# SCH___2023-12-28.net
KiCad netlist of a schematic drawn in EasyEDA
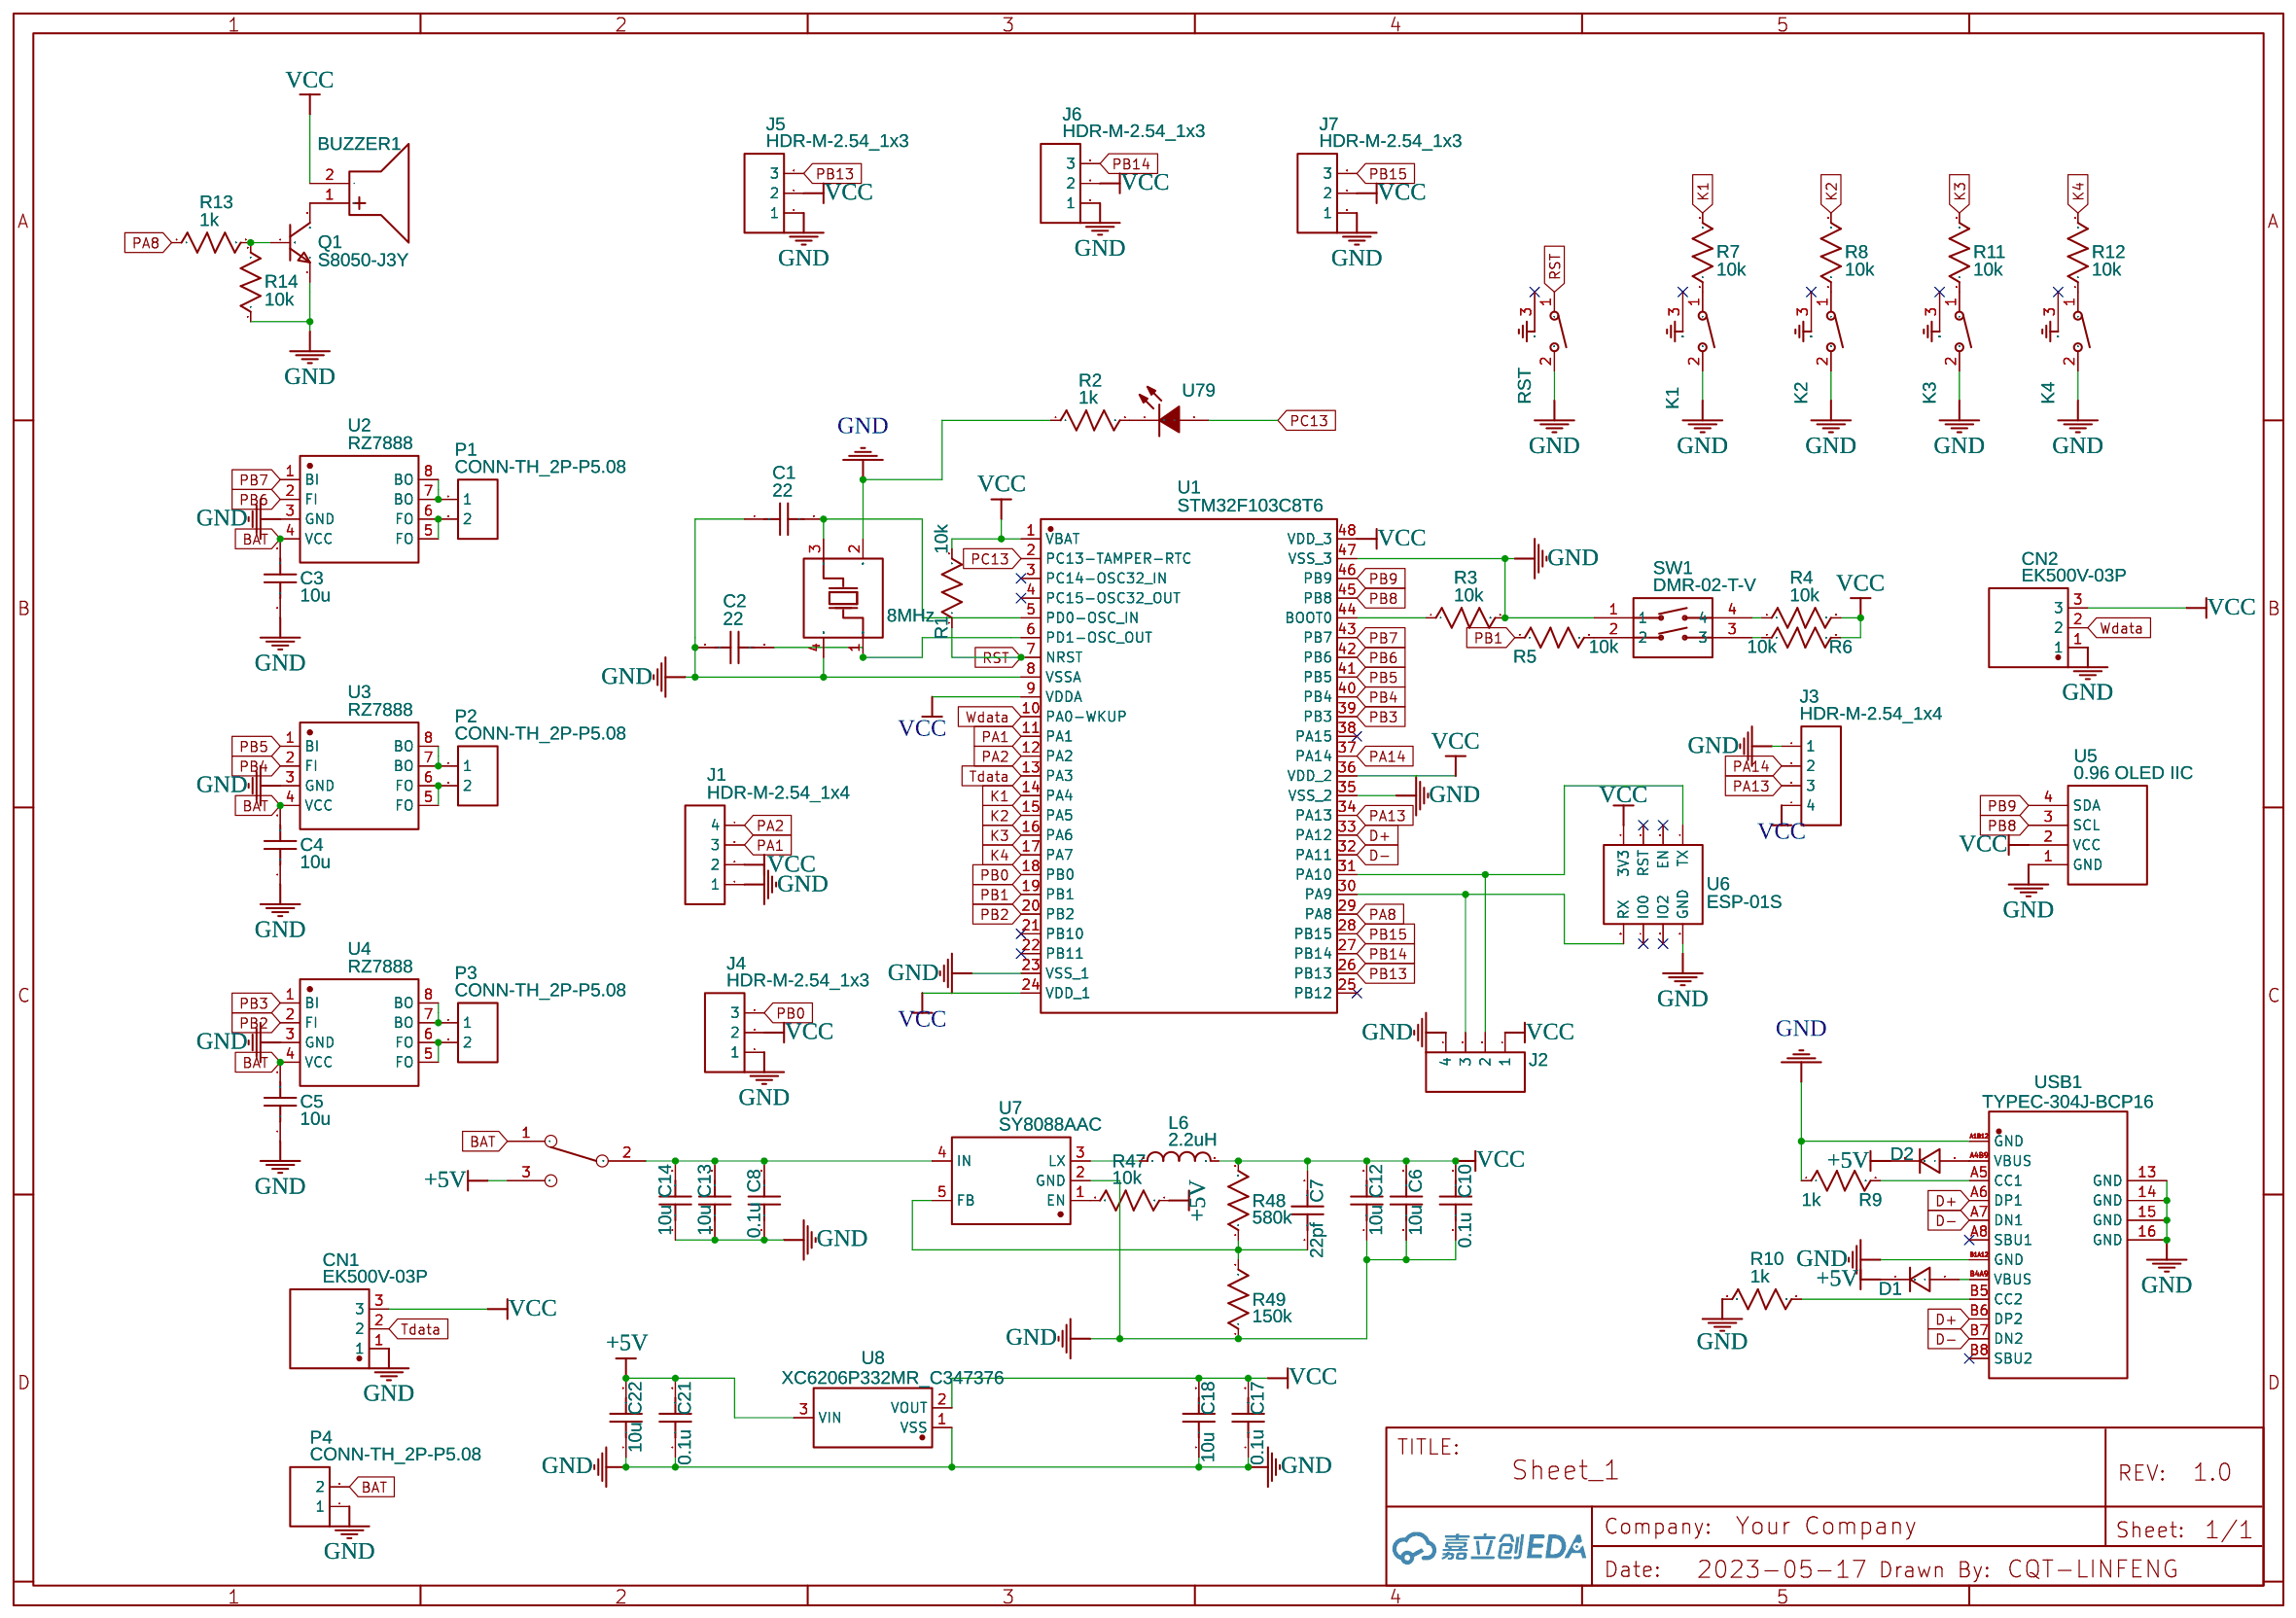
[diagram p0: schematic sheet]

(export (version "E")
  (design (tool "Eeschema 10.0.6"))
  (components
    (comp (ref "BUZZER1")
      (value "有源蜂鸣器直径9*5.5MM3V")
      (fields
        (field (name "BOM_Manufacturer Part") "有源蜂鸣器直径9*5.5mm3V")
        (field (name "BOM_Supplier Part") "C9900012728")
      )
      (libsource (lib "") (part "有源蜂鸣器直径9*5.5MM3V"))
    )
    (comp (ref "C1") (value "22") (libsource (lib "") (part "C_0402_US_1")))
    (comp (ref "C2") (value "22") (libsource (lib "") (part "C_0402_US_1")))
    (comp (ref "C3") (value "10u") (libsource (lib "") (part "C_0402_US")))
    (comp (ref "C4") (value "10u") (libsource (lib "") (part "C_0402_US")))
    (comp (ref "C5") (value "10u") (libsource (lib "") (part "C_0402_US")))
    (comp (ref "C6") (value "10u") (libsource (lib "") (part "C_0402_US")))
    (comp (ref "C7") (value "22pf") (libsource (lib "") (part "C_0402_US")))
    (comp (ref "C8") (value "0.1u") (libsource (lib "") (part "C_0402_US")))
    (comp (ref "C10") (value "0.1u") (libsource (lib "") (part "C_0402_US")))
    (comp (ref "C12") (value "10u") (libsource (lib "") (part "C_0402_US")))
    (comp (ref "C13") (value "10u") (libsource (lib "") (part "C_0402_US")))
    (comp (ref "C14") (value "10u") (libsource (lib "") (part "C_0402_US")))
    (comp (ref "C17") (value "0.1u") (libsource (lib "") (part "C_0402_US")))
    (comp (ref "C18") (value "10u") (libsource (lib "") (part "C_0402_US")))
    (comp (ref "C21") (value "0.1u") (libsource (lib "") (part "C_0402_US")))
    (comp (ref "C22") (value "10u") (libsource (lib "") (part "C_0402_US")))
    (comp (ref "CN1")
      (value "EK500V-03P")
      (fields (field (name "BOM_Supplier Part") "C182803"))
      (libsource (lib "") (part "EK500V-03P"))
    )
    (comp (ref "CN2")
      (value "EK500V-03P")
      (fields (field (name "BOM_Supplier Part") "C182803"))
      (libsource (lib "") (part "EK500V-03P"))
    )
    (comp (ref "D1")
      (value "1N4148WSG")
      (fields (field (name "BOM_Supplier Part") "C380926"))
      (libsource (lib "") (part "1N4148WSG"))
    )
    (comp (ref "D2")
      (value "1N4148WSG")
      (fields (field (name "BOM_Supplier Part") "C380926"))
      (libsource (lib "") (part "1N4148WSG"))
    )
    (comp (ref "ENABLE1") (value "SS-12D00-G4") (libsource (lib "") (part "SS-12D00-G4")))
    (comp (ref "J1")
      (value "HDR-M-2.54_1x4")
      (fields (field (name "BOM_Supplier Part") "C124378"))
      (libsource (lib "") (part "HDR-M-2.54_1x4_1"))
    )
    (comp (ref "J2")
      (value "HDR-M-2.54_1x4")
      (fields (field (name "BOM_Supplier Part") "C124378"))
      (libsource (lib "") (part "HDR-M-2.54_1x4"))
    )
    (comp (ref "J3")
      (value "HDR-M-2.54_1x4")
      (fields (field (name "BOM_Supplier Part") "C124378"))
      (libsource (lib "") (part "HDR-M-2.54_1x4_2"))
    )
    (comp (ref "J4")
      (value "HDR-M-2.54_1x3")
      (fields (field (name "BOM_Supplier Part") "C180248"))
      (libsource (lib "") (part "HDR-M-2.54_1x3"))
    )
    (comp (ref "J5")
      (value "HDR-M-2.54_1x3")
      (fields (field (name "BOM_Supplier Part") "C180248"))
      (libsource (lib "") (part "HDR-M-2.54_1x3"))
    )
    (comp (ref "J6")
      (value "HDR-M-2.54_1x3")
      (fields (field (name "BOM_Supplier Part") "C180248"))
      (libsource (lib "") (part "HDR-M-2.54_1x3"))
    )
    (comp (ref "J7")
      (value "HDR-M-2.54_1x3")
      (fields (field (name "BOM_Supplier Part") "C180248"))
      (libsource (lib "") (part "HDR-M-2.54_1x3"))
    )
    (comp (ref "K1") (value "侧按键") (libsource (lib "") (part "侧按键")))
    (comp (ref "K2") (value "侧按键") (libsource (lib "") (part "侧按键")))
    (comp (ref "K3") (value "侧按键") (libsource (lib "") (part "侧按键")))
    (comp (ref "K4") (value "侧按键") (libsource (lib "") (part "侧按键")))
    (comp (ref "L6")
      (value "2.2uH")
      (fields
        (field (name "BOM_Manufacturer Part") "SMTDR32-2R2M")
        (field (name "BOM_Supplier Part") "C326182")
      )
      (libsource (lib "") (part "SMTDR32-2R2M"))
    )
    (comp (ref "P1") (value "CONN-TH_2P-P5.08") (libsource (lib "") (part "CONN-TH_2P-P5.08")))
    (comp (ref "P2") (value "CONN-TH_2P-P5.08") (libsource (lib "") (part "CONN-TH_2P-P5.08")))
    (comp (ref "P3") (value "CONN-TH_2P-P5.08") (libsource (lib "") (part "CONN-TH_2P-P5.08")))
    (comp (ref "P4") (value "CONN-TH_2P-P5.08") (libsource (lib "") (part "CONN-TH_2P-P5.08_1")))
    (comp (ref "Q1")
      (value "S8050-J3Y")
      (fields (field (name "BOM_Supplier Part") "C364312"))
      (libsource (lib "") (part "S8050-J3Y"))
    )
    (comp (ref "R1") (value "10k") (libsource (lib "") (part "R_0402_US")))
    (comp (ref "R2") (value "1k") (libsource (lib "") (part "R_0402_US_1")))
    (comp (ref "R3") (value "10k") (libsource (lib "") (part "R_0402_US_1")))
    (comp (ref "R4") (value "10k") (libsource (lib "") (part "R_0402_US_1")))
    (comp (ref "R5") (value "10k") (libsource (lib "") (part "R_0402_US_1")))
    (comp (ref "R6") (value "10k") (libsource (lib "") (part "R_0402_US_1")))
    (comp (ref "R7") (value "10k") (libsource (lib "") (part "R_0402_US")))
    (comp (ref "R8") (value "10k") (libsource (lib "") (part "R_0402_US")))
    (comp (ref "R9") (value "1k") (libsource (lib "") (part "R_0402_US_1")))
    (comp (ref "R10") (value "1k") (libsource (lib "") (part "R_0402_US_1")))
    (comp (ref "R11") (value "10k") (libsource (lib "") (part "R_0402_US")))
    (comp (ref "R12") (value "10k") (libsource (lib "") (part "R_0402_US")))
    (comp (ref "R13") (value "1k") (libsource (lib "") (part "R_0402_US_1")))
    (comp (ref "R14") (value "10k") (libsource (lib "") (part "R_0402_US")))
    (comp (ref "R47") (value "10k") (libsource (lib "") (part "R_0402_US_2")))
    (comp (ref "R48") (value "580k") (libsource (lib "") (part "R_0402_US")))
    (comp (ref "R49") (value "150k") (libsource (lib "") (part "R_0402_US")))
    (comp (ref "RST") (value "侧按键") (libsource (lib "") (part "侧按键_1")))
    (comp (ref "SW1")
      (value "DMR-02-T-V")
      (fields (field (name "BOM_Supplier Part") "C139554"))
      (libsource (lib "") (part "DMR-02-T-V"))
    )
    (comp (ref "U1")
      (value "STM32F103C8T6")
      (fields (field (name "BOM_Supplier Part") "C8734"))
      (libsource (lib "") (part "STM32F103C8T6"))
    )
    (comp (ref "U2")
      (value "RZ7888")
      (fields (field (name "BOM_Supplier Part") "C94177"))
      (libsource (lib "") (part "RZ7888"))
    )
    (comp (ref "U3")
      (value "RZ7888")
      (fields (field (name "BOM_Supplier Part") "C94177"))
      (libsource (lib "") (part "RZ7888"))
    )
    (comp (ref "U4")
      (value "RZ7888")
      (fields (field (name "BOM_Supplier Part") "C94177"))
      (libsource (lib "") (part "RZ7888"))
    )
    (comp (ref "U5") (value "0.96 OLED IIC") (libsource (lib "") (part "0.96 OLED IIC")))
    (comp (ref "U6") (value "ESP-01S") (libsource (lib "") (part "ESP-01S")))
    (comp (ref "U7")
      (value "SY8088AAC")
      (fields (field (name "BOM_Supplier Part") "C79313"))
      (libsource (lib "") (part "SY8088AAC"))
    )
    (comp (ref "U8")
      (value "XC6206P332MR_C347376")
      (fields
        (field (name "BOM_Manufacturer Part") "XC6206P332MR")
        (field (name "BOM_Supplier Part") "C347376")
      )
      (libsource (lib "") (part "XC6206P332MR_C347376"))
    )
    (comp (ref "U79")
      (value "GBG-C281TBKT")
      (fields (field (name "BOM_Supplier Part") "C2892152"))
      (libsource (lib "") (part "GBG-C281TBKT"))
    )
    (comp (ref "USB1")
      (value "TYPEC-304J-BCP16")
      (fields (field (name "BOM_Supplier Part") "C2835315"))
      (libsource (lib "") (part "TYPEC-304J-BCP16"))
    )
    (comp (ref "X1")
      (value "8MHz")
      (fields
        (field (name "BOM_Manufacturer Part") "X1E000021037500")
        (field (name "BOM_Supplier Part") "C89379")
      )
      (libsource (lib "") (part "X1E0000210375000G"))
    )
  )
  (nets
    (net (code "1") (name "+5V") (class "Default")
      (node (ref "C21") (pin "2") (pinfunction "2_2") (pintype "unspecified"))
      (node (ref "C22") (pin "2") (pinfunction "2_2") (pintype "unspecified"))
      (node (ref "D1") (pin "1") (pinfunction "C_1") (pintype "unspecified"))
      (node (ref "D2") (pin "1") (pinfunction "C_1") (pintype "unspecified"))
      (node (ref "ENABLE1") (pin "3") (pinfunction "3_3") (pintype "unspecified"))
      (node (ref "R47") (pin "1") (pinfunction "1_1") (pintype "unspecified"))
      (node (ref "U8") (pin "3") (pinfunction "VIN_3") (pintype "unspecified"))
    )
    (net (code "2") (name "BAT") (class "Default")
      (node (ref "C3") (pin "2") (pinfunction "2_2") (pintype "unspecified"))
      (node (ref "C4") (pin "2") (pinfunction "2_2") (pintype "unspecified"))
      (node (ref "C5") (pin "2") (pinfunction "2_2") (pintype "unspecified"))
      (node (ref "ENABLE1") (pin "1") (pinfunction "1_1") (pintype "unspecified"))
      (node (ref "P4") (pin "2") (pinfunction "2_2") (pintype "unspecified"))
      (node (ref "U2") (pin "4") (pinfunction "VCC_4") (pintype "unspecified"))
      (node (ref "U3") (pin "4") (pinfunction "VCC_4") (pintype "unspecified"))
      (node (ref "U4") (pin "4") (pinfunction "VCC_4") (pintype "unspecified"))
    )
    (net (code "3") (name "D+") (class "Default")
      (node (ref "U1") (pin "33") (pinfunction "PA12_33") (pintype "unspecified"))
      (node (ref "USB1") (pin "A6") (pinfunction "DP1_A6") (pintype "unspecified"))
      (node (ref "USB1") (pin "B6") (pinfunction "DP2_B6") (pintype "unspecified"))
    )
    (net (code "4") (name "D-") (class "Default")
      (node (ref "U1") (pin "32") (pinfunction "PA11_32") (pintype "unspecified"))
      (node (ref "USB1") (pin "A7") (pinfunction "DN1_A7") (pintype "unspecified"))
      (node (ref "USB1") (pin "B7") (pinfunction "DN2_B7") (pintype "unspecified"))
    )
    (net (code "5") (name "GND") (class "Default")
      (node (ref "C1") (pin "1") (pinfunction "1_1") (pintype "unspecified"))
      (node (ref "C10") (pin "1") (pinfunction "1_1") (pintype "unspecified"))
      (node (ref "C12") (pin "1") (pinfunction "1_1") (pintype "unspecified"))
      (node (ref "C13") (pin "1") (pinfunction "1_1") (pintype "unspecified"))
      (node (ref "C14") (pin "1") (pinfunction "1_1") (pintype "unspecified"))
      (node (ref "C17") (pin "1") (pinfunction "1_1") (pintype "unspecified"))
      (node (ref "C18") (pin "1") (pinfunction "1_1") (pintype "unspecified"))
      (node (ref "C2") (pin "1") (pinfunction "1_1") (pintype "unspecified"))
      (node (ref "C21") (pin "1") (pinfunction "1_1") (pintype "unspecified"))
      (node (ref "C22") (pin "1") (pinfunction "1_1") (pintype "unspecified"))
      (node (ref "C3") (pin "1") (pinfunction "1_1") (pintype "unspecified"))
      (node (ref "C4") (pin "1") (pinfunction "1_1") (pintype "unspecified"))
      (node (ref "C5") (pin "1") (pinfunction "1_1") (pintype "unspecified"))
      (node (ref "C6") (pin "1") (pinfunction "1_1") (pintype "unspecified"))
      (node (ref "C8") (pin "1") (pinfunction "1_1") (pintype "unspecified"))
      (node (ref "CN1") (pin "1") (pinfunction "1_1") (pintype "unspecified"))
      (node (ref "CN2") (pin "1") (pinfunction "1_1") (pintype "unspecified"))
      (node (ref "J1") (pin "1") (pinfunction "1_1") (pintype "unspecified"))
      (node (ref "J2") (pin "4") (pinfunction "4_4") (pintype "unspecified"))
      (node (ref "J3") (pin "1") (pinfunction "1_1") (pintype "unspecified"))
      (node (ref "J4") (pin "1") (pinfunction "1_1") (pintype "input"))
      (node (ref "J5") (pin "1") (pinfunction "1_1") (pintype "input"))
      (node (ref "J6") (pin "1") (pinfunction "1_1") (pintype "input"))
      (node (ref "J7") (pin "1") (pinfunction "1_1") (pintype "input"))
      (node (ref "K1") (pin "2") (pinfunction "2_2") (pintype "unspecified"))
      (node (ref "K2") (pin "2") (pinfunction "2_2") (pintype "unspecified"))
      (node (ref "K3") (pin "2") (pinfunction "2_2") (pintype "unspecified"))
      (node (ref "K4") (pin "2") (pinfunction "2_2") (pintype "unspecified"))
      (node (ref "P4") (pin "1") (pinfunction "1_1") (pintype "unspecified"))
      (node (ref "Q1") (pin "2") (pinfunction "E_2") (pintype "unspecified"))
      (node (ref "R10") (pin "1") (pinfunction "1_1") (pintype "unspecified"))
      (node (ref "R14") (pin "1") (pinfunction "1_1") (pintype "unspecified"))
      (node (ref "R2") (pin "1") (pinfunction "1_1") (pintype "unspecified"))
      (node (ref "R3") (pin "2") (pinfunction "2_2") (pintype "unspecified"))
      (node (ref "R49") (pin "1") (pinfunction "1_1") (pintype "unspecified"))
      (node (ref "R9") (pin "1") (pinfunction "1_1") (pintype "unspecified"))
      (node (ref "RST") (pin "2") (pinfunction "2_2") (pintype "unspecified"))
      (node (ref "SW1") (pin "1") (pinfunction "1_1") (pintype "unspecified"))
      (node (ref "U1") (pin "23") (pinfunction "VSS_1_23") (pintype "unspecified"))
      (node (ref "U1") (pin "35") (pinfunction "VSS_2_35") (pintype "unspecified"))
      (node (ref "U1") (pin "47") (pinfunction "VSS_3_47") (pintype "unspecified"))
      (node (ref "U1") (pin "8") (pinfunction "VSSA_8") (pintype "unspecified"))
      (node (ref "U2") (pin "3") (pinfunction "GND_3") (pintype "unspecified"))
      (node (ref "U3") (pin "3") (pinfunction "GND_3") (pintype "unspecified"))
      (node (ref "U4") (pin "3") (pinfunction "GND_3") (pintype "unspecified"))
      (node (ref "U5") (pin "1") (pinfunction "GND_1") (pintype "unspecified"))
      (node (ref "U6") (pin "5") (pinfunction "GND_5") (pintype "unspecified"))
      (node (ref "U7") (pin "2") (pinfunction "GND_2") (pintype "unspecified"))
      (node (ref "U8") (pin "1") (pinfunction "VSS_1") (pintype "unspecified"))
      (node (ref "USB1") (pin "13") (pinfunction "GND_13") (pintype "unspecified"))
      (node (ref "USB1") (pin "14") (pinfunction "GND_14") (pintype "unspecified"))
      (node (ref "USB1") (pin "15") (pinfunction "GND_15") (pintype "unspecified"))
      (node (ref "USB1") (pin "16") (pinfunction "GND_16") (pintype "unspecified"))
      (node (ref "USB1") (pin "A1B12") (pinfunction "GND_A1B12") (pintype "unspecified"))
      (node (ref "USB1") (pin "B1A12") (pinfunction "GND_B1A12") (pintype "unspecified"))
      (node (ref "X1") (pin "2") (pinfunction "GND_2") (pintype "unspecified"))
      (node (ref "X1") (pin "4") (pinfunction "GND_4") (pintype "unspecified"))
    )
    (net (code "6") (name "K1") (class "Default")
      (node (ref "R7") (pin "2") (pinfunction "2_2") (pintype "unspecified"))
      (node (ref "U1") (pin "14") (pinfunction "PA4_14") (pintype "unspecified"))
    )
    (net (code "7") (name "K2") (class "Default")
      (node (ref "R8") (pin "2") (pinfunction "2_2") (pintype "unspecified"))
      (node (ref "U1") (pin "15") (pinfunction "PA5_15") (pintype "unspecified"))
    )
    (net (code "8") (name "K3") (class "Default")
      (node (ref "R11") (pin "2") (pinfunction "2_2") (pintype "unspecified"))
      (node (ref "U1") (pin "16") (pinfunction "PA6_16") (pintype "unspecified"))
    )
    (net (code "9") (name "K4") (class "Default")
      (node (ref "R12") (pin "2") (pinfunction "2_2") (pintype "unspecified"))
      (node (ref "U1") (pin "17") (pinfunction "PA7_17") (pintype "unspecified"))
    )
    (net (code "10") (name "Net-(BUZZER1-+)") (class "Default")
      (node (ref "BUZZER1") (pin "1") (pinfunction "+_1") (pintype "unspecified"))
      (node (ref "Q1") (pin "3") (pinfunction "C_3") (pintype "unspecified"))
    )
    (net (code "11") (name "Net-(D1-A)") (class "Default")
      (node (ref "D1") (pin "2") (pinfunction "A_2") (pintype "unspecified"))
      (node (ref "USB1") (pin "B4A9") (pinfunction "VBUS_B4A9") (pintype "unspecified"))
    )
    (net (code "12") (name "Net-(D2-A)") (class "Default")
      (node (ref "D2") (pin "2") (pinfunction "A_2") (pintype "unspecified"))
      (node (ref "USB1") (pin "A4B9") (pinfunction "VBUS_A4B9") (pintype "unspecified"))
    )
    (net (code "13") (name "Net-(K1-Pad1)") (class "Default")
      (node (ref "K1") (pin "1") (pinfunction "1_1") (pintype "unspecified"))
      (node (ref "R7") (pin "1") (pinfunction "1_1") (pintype "unspecified"))
    )
    (net (code "14") (name "Net-(K2-Pad1)") (class "Default")
      (node (ref "K2") (pin "1") (pinfunction "1_1") (pintype "unspecified"))
      (node (ref "R8") (pin "1") (pinfunction "1_1") (pintype "unspecified"))
    )
    (net (code "15") (name "Net-(K3-Pad1)") (class "Default")
      (node (ref "K3") (pin "1") (pinfunction "1_1") (pintype "unspecified"))
      (node (ref "R11") (pin "1") (pinfunction "1_1") (pintype "unspecified"))
    )
    (net (code "16") (name "Net-(K4-Pad1)") (class "Default")
      (node (ref "K4") (pin "1") (pinfunction "1_1") (pintype "unspecified"))
      (node (ref "R12") (pin "1") (pinfunction "1_1") (pintype "unspecified"))
    )
    (net (code "17") (name "Net-(P1-Pad1)") (class "Default")
      (node (ref "P1") (pin "1") (pinfunction "1_1") (pintype "unspecified"))
      (node (ref "U2") (pin "7") (pinfunction "BO_7") (pintype "unspecified"))
      (node (ref "U2") (pin "8") (pinfunction "BO_8") (pintype "unspecified"))
    )
    (net (code "18") (name "Net-(P1-Pad2)") (class "Default")
      (node (ref "P1") (pin "2") (pinfunction "2_2") (pintype "unspecified"))
      (node (ref "U2") (pin "5") (pinfunction "FO_5") (pintype "unspecified"))
      (node (ref "U2") (pin "6") (pinfunction "FO_6") (pintype "unspecified"))
    )
    (net (code "19") (name "Net-(P2-Pad1)") (class "Default")
      (node (ref "P2") (pin "1") (pinfunction "1_1") (pintype "unspecified"))
      (node (ref "U3") (pin "7") (pinfunction "BO_7") (pintype "unspecified"))
      (node (ref "U3") (pin "8") (pinfunction "BO_8") (pintype "unspecified"))
    )
    (net (code "20") (name "Net-(P2-Pad2)") (class "Default")
      (node (ref "P2") (pin "2") (pinfunction "2_2") (pintype "unspecified"))
      (node (ref "U3") (pin "5") (pinfunction "FO_5") (pintype "unspecified"))
      (node (ref "U3") (pin "6") (pinfunction "FO_6") (pintype "unspecified"))
    )
    (net (code "21") (name "Net-(P3-Pad1)") (class "Default")
      (node (ref "P3") (pin "1") (pinfunction "1_1") (pintype "unspecified"))
      (node (ref "U4") (pin "7") (pinfunction "BO_7") (pintype "unspecified"))
      (node (ref "U4") (pin "8") (pinfunction "BO_8") (pintype "unspecified"))
    )
    (net (code "22") (name "Net-(P3-Pad2)") (class "Default")
      (node (ref "P3") (pin "2") (pinfunction "2_2") (pintype "unspecified"))
      (node (ref "U4") (pin "5") (pinfunction "FO_5") (pintype "unspecified"))
      (node (ref "U4") (pin "6") (pinfunction "FO_6") (pintype "unspecified"))
    )
    (net (code "23") (name "Net-(Q1-B)") (class "Default")
      (node (ref "Q1") (pin "1") (pinfunction "B_1") (pintype "unspecified"))
      (node (ref "R13") (pin "2") (pinfunction "2_2") (pintype "unspecified"))
      (node (ref "R14") (pin "2") (pinfunction "2_2") (pintype "unspecified"))
    )
    (net (code "24") (name "Net-(R4-Pad1)") (class "Default")
      (node (ref "R4") (pin "1") (pinfunction "1_1") (pintype "unspecified"))
      (node (ref "SW1") (pin "4") (pinfunction "4_4") (pintype "unspecified"))
    )
    (net (code "25") (name "Net-(R5-Pad2)") (class "Default")
      (node (ref "R5") (pin "2") (pinfunction "2_2") (pintype "unspecified"))
      (node (ref "SW1") (pin "2") (pinfunction "2_2") (pintype "unspecified"))
    )
    (net (code "26") (name "Net-(R6-Pad1)") (class "Default")
      (node (ref "R6") (pin "1") (pinfunction "1_1") (pintype "unspecified"))
      (node (ref "SW1") (pin "3") (pinfunction "3_3") (pintype "unspecified"))
    )
    (net (code "27") (name "Net-(U1-BOOT0)") (class "Default")
      (node (ref "R3") (pin "1") (pinfunction "1_1") (pintype "unspecified"))
      (node (ref "U1") (pin "44") (pinfunction "BOOT0_44") (pintype "unspecified"))
    )
    (net (code "28") (name "Net-(U1-PA9)") (class "Default")
      (node (ref "J2") (pin "3") (pinfunction "3_3") (pintype "unspecified"))
      (node (ref "U1") (pin "30") (pinfunction "PA9_30") (pintype "unspecified"))
      (node (ref "U6") (pin "8") (pinfunction "RX_8") (pintype "unspecified"))
    )
    (net (code "29") (name "Net-(U1-PA10)") (class "Default")
      (node (ref "J2") (pin "2") (pinfunction "2_2") (pintype "unspecified"))
      (node (ref "U1") (pin "31") (pinfunction "PA10_31") (pintype "unspecified"))
      (node (ref "U6") (pin "4") (pinfunction "TX_4") (pintype "unspecified"))
    )
    (net (code "30") (name "Net-(U1-PD0-OSC_IN)") (class "Default")
      (node (ref "C1") (pin "2") (pinfunction "2_2") (pintype "unspecified"))
      (node (ref "U1") (pin "5") (pinfunction "PD0-OSC_IN_5") (pintype "unspecified"))
      (node (ref "X1") (pin "3") (pinfunction "OSC2_3") (pintype "unspecified"))
    )
    (net (code "31") (name "Net-(U1-PD1-OSC_OUT)") (class "Default")
      (node (ref "C2") (pin "2") (pinfunction "2_2") (pintype "unspecified"))
      (node (ref "U1") (pin "6") (pinfunction "PD1-OSC_OUT_6") (pintype "unspecified"))
      (node (ref "X1") (pin "1") (pinfunction "OSC1_1") (pintype "unspecified"))
    )
    (net (code "32") (name "Net-(U7-EN)") (class "Default")
      (node (ref "R47") (pin "2") (pinfunction "2_2") (pintype "unspecified"))
      (node (ref "U7") (pin "1") (pinfunction "EN_1") (pintype "unspecified"))
    )
    (net (code "33") (name "Net-(U7-FB)") (class "Default")
      (node (ref "C7") (pin "1") (pinfunction "1_1") (pintype "unspecified"))
      (node (ref "R48") (pin "1") (pinfunction "1_1") (pintype "unspecified"))
      (node (ref "R49") (pin "2") (pinfunction "2_2") (pintype "unspecified"))
      (node (ref "U7") (pin "5") (pinfunction "FB_5") (pintype "unspecified"))
    )
    (net (code "34") (name "Net-(U7-IN)") (class "Default")
      (node (ref "C13") (pin "2") (pinfunction "2_2") (pintype "unspecified"))
      (node (ref "C14") (pin "2") (pinfunction "2_2") (pintype "unspecified"))
      (node (ref "C8") (pin "2") (pinfunction "2_2") (pintype "unspecified"))
      (node (ref "ENABLE1") (pin "2") (pinfunction "2_2") (pintype "unspecified"))
      (node (ref "U7") (pin "4") (pinfunction "IN_4") (pintype "unspecified"))
    )
    (net (code "35") (name "Net-(U7-LX)") (class "Default")
      (node (ref "L6") (pin "1") (pinfunction "1_1") (pintype "unspecified"))
      (node (ref "U7") (pin "3") (pinfunction "LX_3") (pintype "unspecified"))
    )
    (net (code "36") (name "Net-(U79-C)") (class "Default")
      (node (ref "R2") (pin "2") (pinfunction "2_2") (pintype "unspecified"))
      (node (ref "U79") (pin "1") (pinfunction "C_1") (pintype "unspecified"))
    )
    (net (code "37") (name "Net-(USB1-CC1)") (class "Default")
      (node (ref "R9") (pin "2") (pinfunction "2_2") (pintype "unspecified"))
      (node (ref "USB1") (pin "A5") (pinfunction "CC1_A5") (pintype "unspecified"))
    )
    (net (code "38") (name "Net-(USB1-CC2)") (class "Default")
      (node (ref "R10") (pin "2") (pinfunction "2_2") (pintype "unspecified"))
      (node (ref "USB1") (pin "B5") (pinfunction "CC2_B5") (pintype "unspecified"))
    )
    (net (code "39") (name "PA1") (class "Default")
      (node (ref "J1") (pin "3") (pinfunction "3_3") (pintype "unspecified"))
      (node (ref "U1") (pin "11") (pinfunction "PA1_11") (pintype "unspecified"))
    )
    (net (code "40") (name "PA2") (class "Default")
      (node (ref "J1") (pin "4") (pinfunction "4_4") (pintype "unspecified"))
      (node (ref "U1") (pin "12") (pinfunction "PA2_12") (pintype "unspecified"))
    )
    (net (code "41") (name "PA8") (class "Default")
      (node (ref "R13") (pin "1") (pinfunction "1_1") (pintype "unspecified"))
      (node (ref "U1") (pin "29") (pinfunction "PA8_29") (pintype "unspecified"))
    )
    (net (code "42") (name "PA13") (class "Default")
      (node (ref "J3") (pin "3") (pinfunction "3_3") (pintype "unspecified"))
      (node (ref "U1") (pin "34") (pinfunction "PA13_34") (pintype "unspecified"))
    )
    (net (code "43") (name "PA14") (class "Default")
      (node (ref "J3") (pin "2") (pinfunction "2_2") (pintype "unspecified"))
      (node (ref "U1") (pin "37") (pinfunction "PA14_37") (pintype "unspecified"))
    )
    (net (code "44") (name "PB0") (class "Default")
      (node (ref "J4") (pin "3") (pinfunction "3_3") (pintype "input"))
      (node (ref "U1") (pin "18") (pinfunction "PB0_18") (pintype "unspecified"))
    )
    (net (code "45") (name "PB1") (class "Default")
      (node (ref "R5") (pin "1") (pinfunction "1_1") (pintype "unspecified"))
      (node (ref "U1") (pin "19") (pinfunction "PB1_19") (pintype "unspecified"))
    )
    (net (code "46") (name "PB2") (class "Default")
      (node (ref "U1") (pin "20") (pinfunction "PB2_20") (pintype "unspecified"))
      (node (ref "U4") (pin "2") (pinfunction "FI_2") (pintype "unspecified"))
    )
    (net (code "47") (name "PB3") (class "Default")
      (node (ref "U1") (pin "39") (pinfunction "PB3_39") (pintype "unspecified"))
      (node (ref "U4") (pin "1") (pinfunction "BI_1") (pintype "unspecified"))
    )
    (net (code "48") (name "PB4") (class "Default")
      (node (ref "U1") (pin "40") (pinfunction "PB4_40") (pintype "unspecified"))
      (node (ref "U3") (pin "2") (pinfunction "FI_2") (pintype "unspecified"))
    )
    (net (code "49") (name "PB5") (class "Default")
      (node (ref "U1") (pin "41") (pinfunction "PB5_41") (pintype "unspecified"))
      (node (ref "U3") (pin "1") (pinfunction "BI_1") (pintype "unspecified"))
    )
    (net (code "50") (name "PB6") (class "Default")
      (node (ref "U1") (pin "42") (pinfunction "PB6_42") (pintype "unspecified"))
      (node (ref "U2") (pin "2") (pinfunction "FI_2") (pintype "unspecified"))
    )
    (net (code "51") (name "PB7") (class "Default")
      (node (ref "U1") (pin "43") (pinfunction "PB7_43") (pintype "unspecified"))
      (node (ref "U2") (pin "1") (pinfunction "BI_1") (pintype "unspecified"))
    )
    (net (code "52") (name "PB8") (class "Default")
      (node (ref "U1") (pin "45") (pinfunction "PB8_45") (pintype "unspecified"))
      (node (ref "U5") (pin "3") (pinfunction "SCL_3") (pintype "unspecified"))
    )
    (net (code "53") (name "PB9") (class "Default")
      (node (ref "U1") (pin "46") (pinfunction "PB9_46") (pintype "unspecified"))
      (node (ref "U5") (pin "4") (pinfunction "SDA_4") (pintype "unspecified"))
    )
    (net (code "54") (name "PB13") (class "Default")
      (node (ref "J5") (pin "3") (pinfunction "3_3") (pintype "input"))
      (node (ref "U1") (pin "26") (pinfunction "PB13_26") (pintype "unspecified"))
    )
    (net (code "55") (name "PB14") (class "Default")
      (node (ref "J6") (pin "3") (pinfunction "3_3") (pintype "input"))
      (node (ref "U1") (pin "27") (pinfunction "PB14_27") (pintype "unspecified"))
    )
    (net (code "56") (name "PB15") (class "Default")
      (node (ref "J7") (pin "3") (pinfunction "3_3") (pintype "input"))
      (node (ref "U1") (pin "28") (pinfunction "PB15_28") (pintype "unspecified"))
    )
    (net (code "57") (name "PC13") (class "Default")
      (node (ref "U1") (pin "2") (pinfunction "PC13-TAMPER-RTC_2") (pintype "unspecified"))
      (node (ref "U79") (pin "2") (pinfunction "A_2") (pintype "unspecified"))
    )
    (net (code "58") (name "RST") (class "Default")
      (node (ref "R1") (pin "1") (pinfunction "1_1") (pintype "unspecified"))
      (node (ref "RST") (pin "1") (pinfunction "1_1") (pintype "unspecified"))
      (node (ref "U1") (pin "7") (pinfunction "NRST_7") (pintype "unspecified"))
    )
    (net (code "59") (name "Tdata") (class "Default")
      (node (ref "CN1") (pin "2") (pinfunction "2_2") (pintype "unspecified"))
      (node (ref "U1") (pin "13") (pinfunction "PA3_13") (pintype "unspecified"))
    )
    (net (code "60") (name "VCC") (class "Default")
      (node (ref "BUZZER1") (pin "2") (pinfunction "-_2") (pintype "unspecified"))
      (node (ref "C10") (pin "2") (pinfunction "2_2") (pintype "unspecified"))
      (node (ref "C12") (pin "2") (pinfunction "2_2") (pintype "unspecified"))
      (node (ref "C17") (pin "2") (pinfunction "2_2") (pintype "unspecified"))
      (node (ref "C18") (pin "2") (pinfunction "2_2") (pintype "unspecified"))
      (node (ref "C6") (pin "2") (pinfunction "2_2") (pintype "unspecified"))
      (node (ref "C7") (pin "2") (pinfunction "2_2") (pintype "unspecified"))
      (node (ref "CN1") (pin "3") (pinfunction "3_3") (pintype "unspecified"))
      (node (ref "CN2") (pin "3") (pinfunction "3_3") (pintype "unspecified"))
      (node (ref "J1") (pin "2") (pinfunction "2_2") (pintype "unspecified"))
      (node (ref "J2") (pin "1") (pinfunction "1_1") (pintype "unspecified"))
      (node (ref "J3") (pin "4") (pinfunction "4_4") (pintype "unspecified"))
      (node (ref "J4") (pin "2") (pinfunction "2_2") (pintype "input"))
      (node (ref "J5") (pin "2") (pinfunction "2_2") (pintype "input"))
      (node (ref "J6") (pin "2") (pinfunction "2_2") (pintype "input"))
      (node (ref "J7") (pin "2") (pinfunction "2_2") (pintype "input"))
      (node (ref "L6") (pin "2") (pinfunction "2_2") (pintype "unspecified"))
      (node (ref "R1") (pin "2") (pinfunction "2_2") (pintype "unspecified"))
      (node (ref "R4") (pin "2") (pinfunction "2_2") (pintype "unspecified"))
      (node (ref "R48") (pin "2") (pinfunction "2_2") (pintype "unspecified"))
      (node (ref "R6") (pin "2") (pinfunction "2_2") (pintype "unspecified"))
      (node (ref "U1") (pin "1") (pinfunction "VBAT_1") (pintype "unspecified"))
      (node (ref "U1") (pin "24") (pinfunction "VDD_1_24") (pintype "unspecified"))
      (node (ref "U1") (pin "36") (pinfunction "VDD_2_36") (pintype "unspecified"))
      (node (ref "U1") (pin "48") (pinfunction "VDD_3_48") (pintype "unspecified"))
      (node (ref "U1") (pin "9") (pinfunction "VDDA_9") (pintype "unspecified"))
      (node (ref "U5") (pin "2") (pinfunction "VCC_2") (pintype "unspecified"))
      (node (ref "U6") (pin "1") (pinfunction "3V3_1") (pintype "unspecified"))
      (node (ref "U8") (pin "2") (pinfunction "VOUT_2") (pintype "unspecified"))
    )
    (net (code "61") (name "Wdata") (class "Default")
      (node (ref "CN2") (pin "2") (pinfunction "2_2") (pintype "unspecified"))
      (node (ref "U1") (pin "10") (pinfunction "PA0-WKUP_10") (pintype "unspecified"))
    )
    (net (code "62") (name "unconnected-(K1-GND-Pad3)") (class "Default")
      (node (ref "K1") (pin "3") (pinfunction "GND_3") (pintype "unspecified+no_connect"))
    )
    (net (code "63") (name "unconnected-(K2-GND-Pad3)") (class "Default")
      (node (ref "K2") (pin "3") (pinfunction "GND_3") (pintype "unspecified+no_connect"))
    )
    (net (code "64") (name "unconnected-(K3-GND-Pad3)") (class "Default")
      (node (ref "K3") (pin "3") (pinfunction "GND_3") (pintype "unspecified+no_connect"))
    )
    (net (code "65") (name "unconnected-(K4-GND-Pad3)") (class "Default")
      (node (ref "K4") (pin "3") (pinfunction "GND_3") (pintype "unspecified+no_connect"))
    )
    (net (code "66") (name "unconnected-(RST-GND-Pad3)") (class "Default")
      (node (ref "RST") (pin "3") (pinfunction "GND_3") (pintype "unspecified+no_connect"))
    )
    (net (code "67") (name "unconnected-(U1-PA15-Pad38)") (class "Default")
      (node (ref "U1") (pin "38") (pinfunction "PA15_38") (pintype "unspecified+no_connect"))
    )
    (net (code "68") (name "unconnected-(U1-PB10-Pad21)") (class "Default")
      (node (ref "U1") (pin "21") (pinfunction "PB10_21") (pintype "unspecified+no_connect"))
    )
    (net (code "69") (name "unconnected-(U1-PB11-Pad22)") (class "Default")
      (node (ref "U1") (pin "22") (pinfunction "PB11_22") (pintype "unspecified+no_connect"))
    )
    (net (code "70") (name "unconnected-(U1-PB12-Pad25)") (class "Default")
      (node (ref "U1") (pin "25") (pinfunction "PB12_25") (pintype "unspecified+no_connect"))
    )
    (net (code "71") (name "unconnected-(U1-PC14-OSC32_IN-Pad3)") (class "Default")
      (node (ref "U1") (pin "3") (pinfunction "PC14-OSC32_IN_3") (pintype "unspecified+no_connect"))
    )
    (net (code "72") (name "unconnected-(U1-PC15-OSC32_OUT-Pad4)") (class "Default")
      (node (ref "U1") (pin "4") (pinfunction "PC15-OSC32_OUT_4") (pintype "unspecified+no_connect"))
    )
    (net (code "73") (name "unconnected-(U6-EN-Pad3)") (class "Default")
      (node (ref "U6") (pin "3") (pinfunction "EN_3") (pintype "unspecified+no_connect"))
    )
    (net (code "74") (name "unconnected-(U6-IO0-Pad7)") (class "Default")
      (node (ref "U6") (pin "7") (pinfunction "IO0_7") (pintype "unspecified+no_connect"))
    )
    (net (code "75") (name "unconnected-(U6-IO2-Pad6)") (class "Default")
      (node (ref "U6") (pin "6") (pinfunction "IO2_6") (pintype "unspecified+no_connect"))
    )
    (net (code "76") (name "unconnected-(U6-RST-Pad2)") (class "Default")
      (node (ref "U6") (pin "2") (pinfunction "RST_2") (pintype "unspecified+no_connect"))
    )
    (net (code "77") (name "unconnected-(USB1-SBU1-PadA8)") (class "Default")
      (node (ref "USB1") (pin "A8") (pinfunction "SBU1_A8") (pintype "unspecified+no_connect"))
    )
    (net (code "78") (name "unconnected-(USB1-SBU2-PadB8)") (class "Default")
      (node (ref "USB1") (pin "B8") (pinfunction "SBU2_B8") (pintype "unspecified+no_connect"))
    )
  )
)
